# Mirror_ctrl_v1.net
KiCad netlist of a schematic drawn in EAGLE
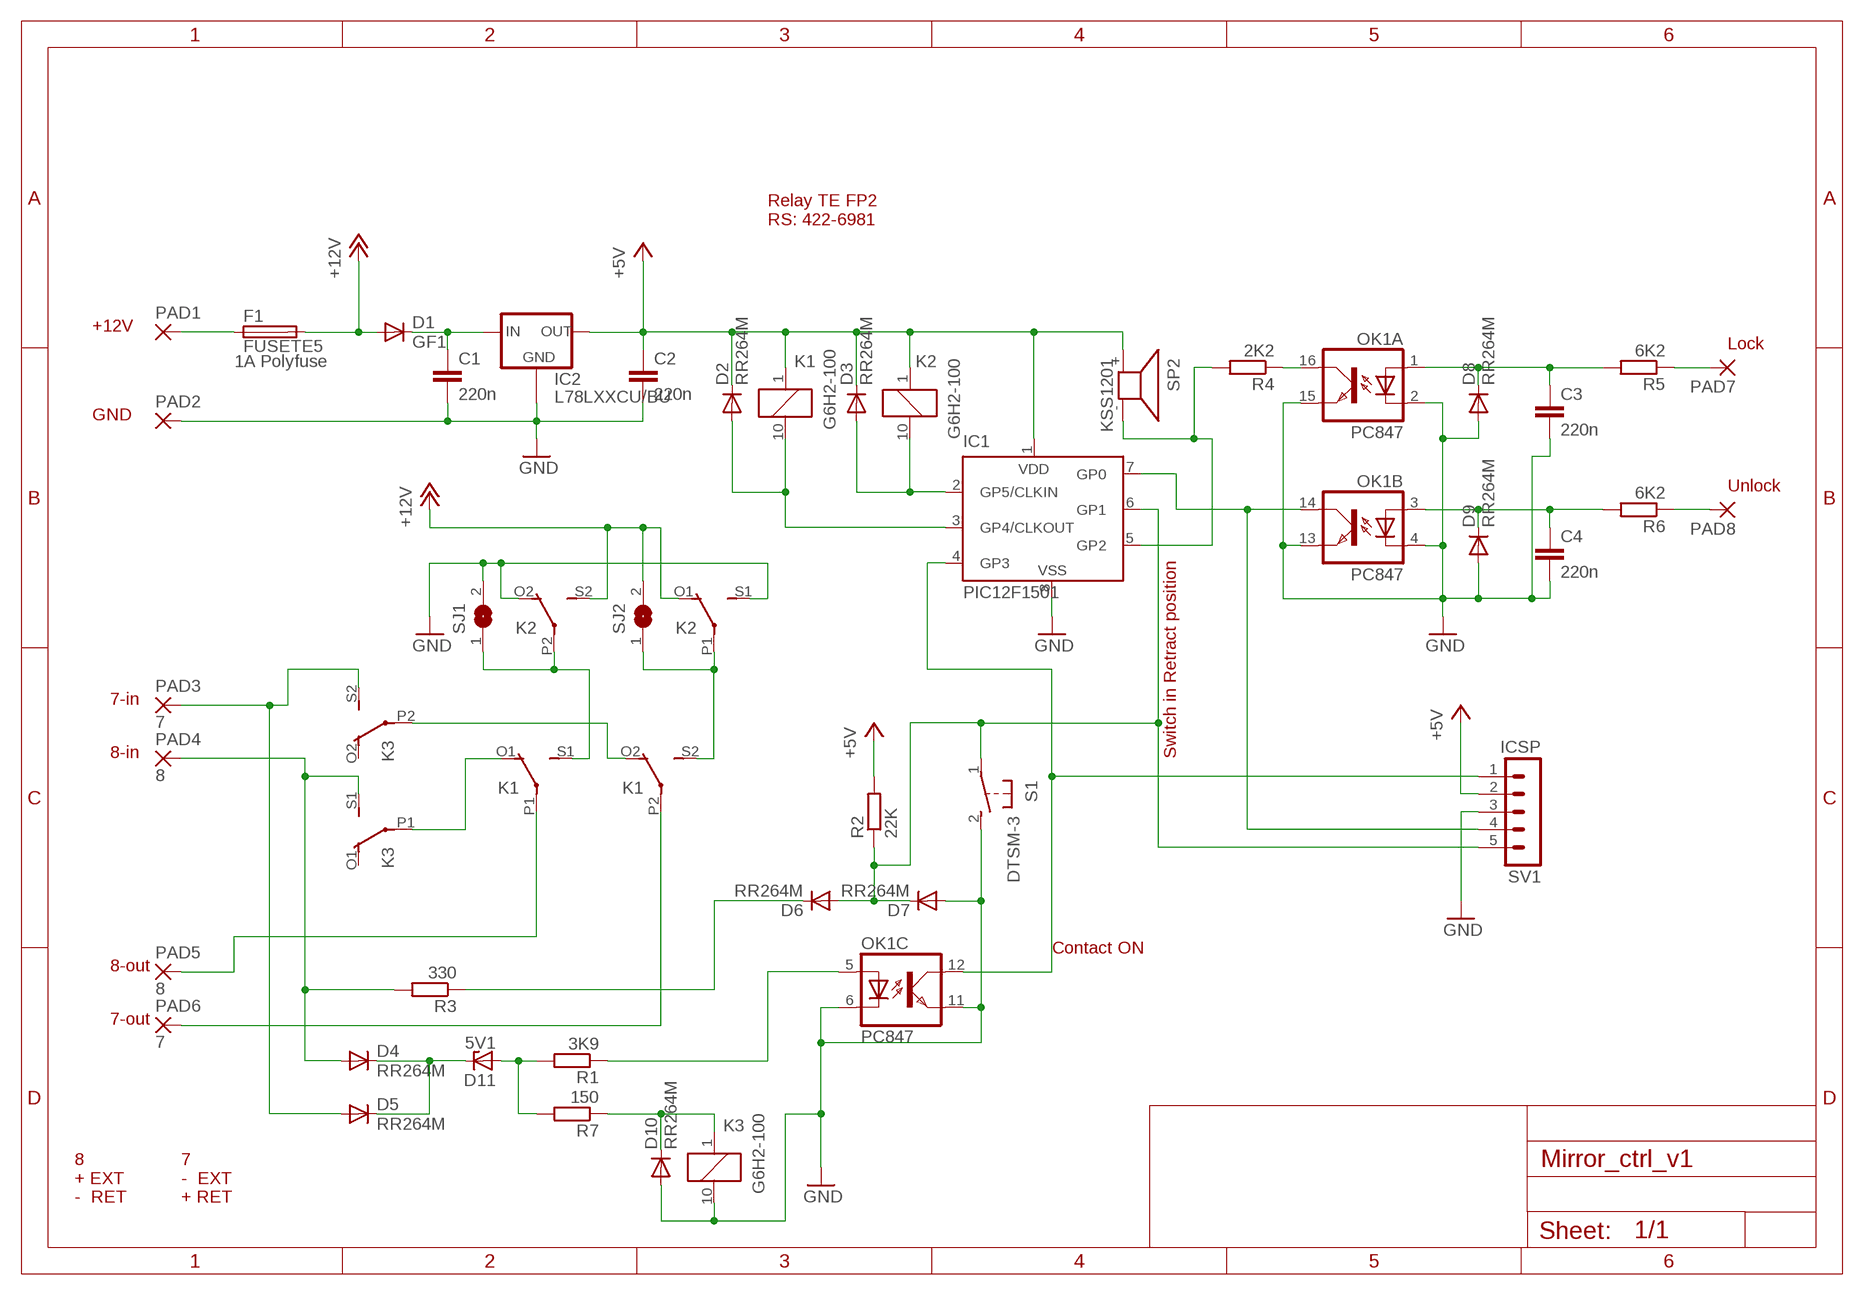
[diagram p0: schematic, sheet 1]

(export (version "E")
  (design (tool "Eeschema 10.0.6"))
  (components
    (comp (ref "C1")
      (value "220n")
      (footprint "eagle-import:C1206")
      (libsource (lib "eagle-import") (part "C-EUC1206"))
    )
    (comp (ref "C2")
      (value "220n")
      (footprint "eagle-import:C1206")
      (libsource (lib "eagle-import") (part "C-EUC1206"))
    )
    (comp (ref "C3")
      (value "220n")
      (footprint "eagle-import:C1206")
      (libsource (lib "eagle-import") (part "C-EUC1206"))
    )
    (comp (ref "C4")
      (value "220n")
      (footprint "eagle-import:C1206")
      (libsource (lib "eagle-import") (part "C-EUC1206"))
    )
    (comp (ref "D1")
      (value "GF1")
      (footprint "eagle-import:DO214BA")
      (libsource (lib "eagle-import") (part "DIODE-DO214BA"))
    )
    (comp (ref "D2")
      (value "RR264M")
      (footprint "eagle-import:SOD-123_MINI-SMA")
      (libsource (lib "eagle-import") (part "CGRM400-G1"))
    )
    (comp (ref "D3")
      (value "RR264M")
      (footprint "eagle-import:SOD-123_MINI-SMA")
      (libsource (lib "eagle-import") (part "CGRM400-G1"))
    )
    (comp (ref "D4")
      (value "RR264M")
      (footprint "eagle-import:SOD-123_MINI-SMA")
      (libsource (lib "eagle-import") (part "CGRM400-G1"))
    )
    (comp (ref "D5")
      (value "RR264M")
      (footprint "eagle-import:SOD-123_MINI-SMA")
      (libsource (lib "eagle-import") (part "CGRM400-G1"))
    )
    (comp (ref "D6")
      (value "RR264M")
      (footprint "eagle-import:SOD-123_MINI-SMA")
      (libsource (lib "eagle-import") (part "CGRM400-G1"))
    )
    (comp (ref "D7")
      (value "RR264M")
      (footprint "eagle-import:SOD-123_MINI-SMA")
      (libsource (lib "eagle-import") (part "CGRM400-G1"))
    )
    (comp (ref "D8")
      (value "RR264M")
      (footprint "eagle-import:SOD-123_MINI-SMA")
      (libsource (lib "eagle-import") (part "CGRM400-G1"))
    )
    (comp (ref "D9")
      (value "RR264M")
      (footprint "eagle-import:SOD-123_MINI-SMA")
      (libsource (lib "eagle-import") (part "CGRM400-G1"))
    )
    (comp (ref "D10")
      (value "RR264M")
      (footprint "eagle-import:SOD-123_MINI-SMA")
      (libsource (lib "eagle-import") (part "CGRM400-G1"))
    )
    (comp (ref "D11")
      (value "5V1")
      (footprint "eagle-import:SOD80C")
      (libsource (lib "eagle-import") (part "ZENER-DIODESOD80C"))
    )
    (comp (ref "F1")
      (value "FUSETE5")
      (footprint "eagle-import:TE5")
      (libsource (lib "eagle-import") (part "FUSETE5"))
    )
    (comp (ref "IC1")
      (value "PIC12F1501")
      (footprint "eagle-import:DIL8")
      (fields (field (name "MF") "MICROCHIP") (field (name "MPN") "PIC12F675-E/P"))
      (libsource (lib "eagle-import") (part "PIC12F6P75"))
    )
    (comp (ref "IC2")
      (value "L78LXXCU/BU")
      (footprint "eagle-import:SOT89")
      (libsource (lib "eagle-import") (part "L78LXXCU/BU"))
    )
    (comp (ref "K1")
      (value "G6H2-100")
      (footprint "eagle-import:G6H2-100")
      (libsource (lib "eagle-import") (part "G6H2-100"))
    )
    (comp (ref "K2")
      (value "G6H2-100")
      (footprint "eagle-import:G6H2-100")
      (libsource (lib "eagle-import") (part "G6H2-100"))
    )
    (comp (ref "K3")
      (value "G6H2-100")
      (footprint "eagle-import:G6H2-100")
      (libsource (lib "eagle-import") (part "G6H2-100"))
    )
    (comp (ref "OK1")
      (value "PC847")
      (footprint "eagle-import:DIL16")
      (libsource (lib "eagle-import") (part "PC847"))
    )
    (comp (ref "PAD1")
      (value "3,81/1,4")
      (footprint "eagle-import:3,81_1,4")
      (libsource (lib "eagle-import") (part "3,81/1,4"))
    )
    (comp (ref "PAD2")
      (value "3,81/1,4")
      (footprint "eagle-import:3,81_1,4")
      (libsource (lib "eagle-import") (part "3,81/1,4"))
    )
    (comp (ref "PAD3")
      (value "7")
      (footprint "eagle-import:3,81_1,4")
      (libsource (lib "eagle-import") (part "3,81/1,4"))
    )
    (comp (ref "PAD4")
      (value "8")
      (footprint "eagle-import:3,81_1,4")
      (libsource (lib "eagle-import") (part "3,81/1,4"))
    )
    (comp (ref "PAD5")
      (value "8")
      (footprint "eagle-import:3,81_1,4")
      (libsource (lib "eagle-import") (part "3,81/1,4"))
    )
    (comp (ref "PAD6")
      (value "7")
      (footprint "eagle-import:3,81_1,4")
      (libsource (lib "eagle-import") (part "3,81/1,4"))
    )
    (comp (ref "PAD7")
      (value "3,81/1,4")
      (footprint "eagle-import:3,81_1,4")
      (libsource (lib "eagle-import") (part "3,81/1,4"))
    )
    (comp (ref "PAD8")
      (value "3,81/1,4")
      (footprint "eagle-import:3,81_1,4")
      (libsource (lib "eagle-import") (part "3,81/1,4"))
    )
    (comp (ref "R1")
      (value "3K9")
      (footprint "eagle-import:R1206")
      (libsource (lib "eagle-import") (part "R-EU_R1206"))
    )
    (comp (ref "R2")
      (value "22K")
      (footprint "eagle-import:R1206")
      (libsource (lib "eagle-import") (part "R-EU_R1206"))
    )
    (comp (ref "R3")
      (value "330")
      (footprint "eagle-import:R1206")
      (libsource (lib "eagle-import") (part "R-EU_R1206"))
    )
    (comp (ref "R4")
      (value "2K2")
      (footprint "eagle-import:R1206")
      (libsource (lib "eagle-import") (part "R-EU_R1206"))
    )
    (comp (ref "R5")
      (value "6K2")
      (footprint "eagle-import:R1206")
      (libsource (lib "eagle-import") (part "R-EU_R1206"))
    )
    (comp (ref "R6")
      (value "6K2")
      (footprint "eagle-import:R1206")
      (libsource (lib "eagle-import") (part "R-EU_R1206"))
    )
    (comp (ref "R7")
      (value "150")
      (footprint "eagle-import:R1206")
      (libsource (lib "eagle-import") (part "R-EU_R1206"))
    )
    (comp (ref "S1")
      (value "DTSM-3")
      (footprint "eagle-import:DTSM-3")
      (libsource (lib "eagle-import") (part "DTSM-3"))
    )
    (comp (ref "SJ1") (value "SJ") (footprint "eagle-import:SJ") (libsource (lib "eagle-import") (part "SJ")))
    (comp (ref "SJ2") (value "SJ") (footprint "eagle-import:SJ") (libsource (lib "eagle-import") (part "SJ")))
    (comp (ref "SP2")
      (value "KSS1201")
      (footprint "eagle-import:KSS1201")
      (libsource (lib "eagle-import") (part "KSS1201"))
    )
    (comp (ref "SV1")
      (value "ICSP")
      (footprint "eagle-import:MA05-1")
      (libsource (lib "eagle-import") (part "MA05-1"))
    )
  )
  (nets
    (net (code "1") (name "+5V") (class "Default")
      (node (ref "C2") (pin "1") (pinfunction "1_1") (pintype "passive"))
      (node (ref "D2") (pin "C") (pinfunction "C_C") (pintype "passive"))
      (node (ref "D3") (pin "C") (pinfunction "C_C") (pintype "passive"))
      (node (ref "IC1") (pin "1") (pinfunction "VDD_1") (pintype "power_in"))
      (node (ref "IC2") (pin "1") (pinfunction "OUT_1") (pintype "passive"))
      (node (ref "K1") (pin "1") (pinfunction "1_1") (pintype "passive"))
      (node (ref "K2") (pin "1") (pinfunction "1_1") (pintype "passive"))
      (node (ref "R2") (pin "2") (pinfunction "2_2") (pintype "passive"))
      (node (ref "SP2") (pin "+") (pinfunction "1_+") (pintype "passive"))
      (node (ref "SV1") (pin "2") (pinfunction "2_2") (pintype "passive"))
    )
    (net (code "2") (name "+12V") (class "Default")
      (node (ref "D1") (pin "A") (pinfunction "A_A") (pintype "passive"))
      (node (ref "F1") (pin "2") (pinfunction "2_2") (pintype "passive"))
      (node (ref "K2") (pin "O1") (pinfunction "O_O1") (pintype "passive"))
      (node (ref "K2") (pin "S2") (pinfunction "S_S2") (pintype "passive"))
      (node (ref "SJ2") (pin "2") (pinfunction "2_2") (pintype "passive"))
    )
    (net (code "3") (name "GND") (class "Default")
      (node (ref "C1") (pin "2") (pinfunction "2_2") (pintype "passive"))
      (node (ref "C2") (pin "2") (pinfunction "2_2") (pintype "passive"))
      (node (ref "C3") (pin "2") (pinfunction "2_2") (pintype "passive"))
      (node (ref "C4") (pin "2") (pinfunction "2_2") (pintype "passive"))
      (node (ref "D10") (pin "A") (pinfunction "A_A") (pintype "passive"))
      (node (ref "D7") (pin "A") (pinfunction "A_A") (pintype "passive"))
      (node (ref "D8") (pin "A") (pinfunction "A_A") (pintype "passive"))
      (node (ref "D9") (pin "A") (pinfunction "A_A") (pintype "passive"))
      (node (ref "IC1") (pin "8") (pinfunction "VSS_8") (pintype "power_in"))
      (node (ref "IC2") (pin "4") (pinfunction "GND1_4") (pintype "input"))
      (node (ref "K2") (pin "O2") (pinfunction "O_O2") (pintype "passive"))
      (node (ref "K2") (pin "S1") (pinfunction "S_S1") (pintype "passive"))
      (node (ref "K3") (pin "10") (pinfunction "2_10") (pintype "passive"))
      (node (ref "OK1") (pin "11") (pinfunction "EMIT_11") (pintype "passive"))
      (node (ref "OK1") (pin "13") (pinfunction "EMIT_13") (pintype "passive"))
      (node (ref "OK1") (pin "15") (pinfunction "EMIT_15") (pintype "passive"))
      (node (ref "OK1") (pin "2") (pinfunction "C_2") (pintype "passive"))
      (node (ref "OK1") (pin "4") (pinfunction "C_4") (pintype "passive"))
      (node (ref "OK1") (pin "6") (pinfunction "C_6") (pintype "passive"))
      (node (ref "PAD2") (pin "1") (pinfunction "P_1") (pintype "passive"))
      (node (ref "S1") (pin "2") (pinfunction "2_2") (pintype "passive"))
      (node (ref "SJ1") (pin "2") (pinfunction "2_2") (pintype "passive"))
      (node (ref "SV1") (pin "3") (pinfunction "3_3") (pintype "passive"))
    )
    (net (code "4") (name "Net-(D6-PadC)") (class "Default")
      (node (ref "D6") (pin "C") (pinfunction "C_C") (pintype "passive"))
      (node (ref "R3") (pin "1") (pinfunction "1_1") (pintype "passive"))
    )
    (net (code "5") (name "Net-(D10-PadC)") (class "Default")
      (node (ref "D10") (pin "C") (pinfunction "C_C") (pintype "passive"))
      (node (ref "K3") (pin "1") (pinfunction "1_1") (pintype "passive"))
      (node (ref "R7") (pin "1") (pinfunction "1_1") (pintype "passive"))
    )
    (net (code "6") (name "Net-(D11-PadA)") (class "Default")
      (node (ref "D11") (pin "A") (pinfunction "A_A") (pintype "passive"))
      (node (ref "R1") (pin "2") (pinfunction "2_2") (pintype "passive"))
      (node (ref "R7") (pin "2") (pinfunction "2_2") (pintype "passive"))
    )
    (net (code "7") (name "Net-(D11-PadC)") (class "Default")
      (node (ref "D11") (pin "C") (pinfunction "C_C") (pintype "passive"))
      (node (ref "D4") (pin "C") (pinfunction "C_C") (pintype "passive"))
      (node (ref "D5") (pin "C") (pinfunction "C_C") (pintype "passive"))
    )
    (net (code "8") (name "Net-(IC1-GP0)") (class "Default")
      (node (ref "IC1") (pin "7") (pinfunction "GP0_7") (pintype "bidirectional"))
      (node (ref "OK1") (pin "14") (pinfunction "COL_14") (pintype "passive"))
      (node (ref "SV1") (pin "4") (pinfunction "4_4") (pintype "passive"))
    )
    (net (code "9") (name "Net-(IC1-GP1)") (class "Default")
      (node (ref "D6") (pin "A") (pinfunction "A_A") (pintype "passive"))
      (node (ref "D7") (pin "C") (pinfunction "C_C") (pintype "passive"))
      (node (ref "IC1") (pin "6") (pinfunction "GP1_6") (pintype "bidirectional"))
      (node (ref "R2") (pin "1") (pinfunction "1_1") (pintype "passive"))
      (node (ref "S1") (pin "1") (pinfunction "1_1") (pintype "passive"))
      (node (ref "SV1") (pin "5") (pinfunction "5_5") (pintype "passive"))
    )
    (net (code "10") (name "Net-(IC1-GP2)") (class "Default")
      (node (ref "IC1") (pin "5") (pinfunction "GP2_5") (pintype "bidirectional"))
      (node (ref "R4") (pin "2") (pinfunction "2_2") (pintype "passive"))
      (node (ref "SP2") (pin "-") (pinfunction "2_-") (pintype "passive"))
    )
    (net (code "11") (name "Net-(IC1-GP3)") (class "Default")
      (node (ref "IC1") (pin "4") (pinfunction "GP3_4") (pintype "input"))
      (node (ref "OK1") (pin "12") (pinfunction "COL_12") (pintype "passive"))
      (node (ref "SV1") (pin "1") (pinfunction "1_1") (pintype "passive"))
    )
    (net (code "12") (name "Net-(IC1-GP4{slash}CLKOUT)") (class "Default")
      (node (ref "D2") (pin "A") (pinfunction "A_A") (pintype "passive"))
      (node (ref "IC1") (pin "3") (pinfunction "GP4/CLKOUT_3") (pintype "bidirectional"))
      (node (ref "K1") (pin "10") (pinfunction "2_10") (pintype "passive"))
    )
    (net (code "13") (name "Net-(IC1-GP5{slash}CLKIN)") (class "Default")
      (node (ref "D3") (pin "A") (pinfunction "A_A") (pintype "passive"))
      (node (ref "IC1") (pin "2") (pinfunction "GP5/CLKIN_2") (pintype "bidirectional"))
      (node (ref "K2") (pin "10") (pinfunction "2_10") (pintype "passive"))
    )
    (net (code "14") (name "Net-(IC2-IN)") (class "Default")
      (node (ref "C1") (pin "1") (pinfunction "1_1") (pintype "passive"))
      (node (ref "D1") (pin "C") (pinfunction "C_C") (pintype "passive"))
      (node (ref "IC2") (pin "3") (pinfunction "IN_3") (pintype "input"))
    )
    (net (code "15") (name "Net-(K1B-O)") (class "Default")
      (node (ref "K1") (pin "O1") (pinfunction "O_O1") (pintype "passive"))
      (node (ref "K3") (pin "P1") (pinfunction "P_P1") (pintype "passive"))
    )
    (net (code "16") (name "Net-(K1B-P)") (class "Default")
      (node (ref "K1") (pin "P1") (pinfunction "P_P1") (pintype "passive"))
      (node (ref "PAD5") (pin "1") (pinfunction "P_1") (pintype "passive"))
    )
    (net (code "17") (name "Net-(K1B-S)") (class "Default")
      (node (ref "K1") (pin "S1") (pinfunction "S_S1") (pintype "passive"))
      (node (ref "K2") (pin "P2") (pinfunction "P_P2") (pintype "passive"))
      (node (ref "SJ1") (pin "1") (pinfunction "1_1") (pintype "passive"))
    )
    (net (code "18") (name "Net-(K1C-O)") (class "Default")
      (node (ref "K1") (pin "O2") (pinfunction "O_O2") (pintype "passive"))
      (node (ref "K3") (pin "P2") (pinfunction "P_P2") (pintype "passive"))
    )
    (net (code "19") (name "Net-(K1C-P)") (class "Default")
      (node (ref "K1") (pin "P2") (pinfunction "P_P2") (pintype "passive"))
      (node (ref "PAD6") (pin "1") (pinfunction "P_1") (pintype "passive"))
    )
    (net (code "20") (name "Net-(K1C-S)") (class "Default")
      (node (ref "K1") (pin "S2") (pinfunction "S_S2") (pintype "passive"))
      (node (ref "K2") (pin "P1") (pinfunction "P_P1") (pintype "passive"))
      (node (ref "SJ2") (pin "1") (pinfunction "1_1") (pintype "passive"))
    )
    (net (code "21") (name "Net-(K3B-S)") (class "Default")
      (node (ref "D4") (pin "A") (pinfunction "A_A") (pintype "passive"))
      (node (ref "K3") (pin "S1") (pinfunction "S_S1") (pintype "passive"))
      (node (ref "PAD4") (pin "1") (pinfunction "P_1") (pintype "passive"))
      (node (ref "R3") (pin "2") (pinfunction "2_2") (pintype "passive"))
    )
    (net (code "22") (name "Net-(K3C-S)") (class "Default")
      (node (ref "D5") (pin "A") (pinfunction "A_A") (pintype "passive"))
      (node (ref "K3") (pin "S2") (pinfunction "S_S2") (pintype "passive"))
      (node (ref "PAD3") (pin "1") (pinfunction "P_1") (pintype "passive"))
    )
    (net (code "23") (name "Net-(OK1A-A)") (class "Default")
      (node (ref "C3") (pin "1") (pinfunction "1_1") (pintype "passive"))
      (node (ref "D8") (pin "C") (pinfunction "C_C") (pintype "passive"))
      (node (ref "OK1") (pin "1") (pinfunction "A_1") (pintype "passive"))
      (node (ref "R5") (pin "2") (pinfunction "2_2") (pintype "passive"))
    )
    (net (code "24") (name "Net-(OK1A-COL)") (class "Default")
      (node (ref "OK1") (pin "16") (pinfunction "COL_16") (pintype "passive"))
      (node (ref "R4") (pin "1") (pinfunction "1_1") (pintype "passive"))
    )
    (net (code "25") (name "Net-(OK1B-A)") (class "Default")
      (node (ref "C4") (pin "1") (pinfunction "1_1") (pintype "passive"))
      (node (ref "D9") (pin "C") (pinfunction "C_C") (pintype "passive"))
      (node (ref "OK1") (pin "3") (pinfunction "A_3") (pintype "passive"))
      (node (ref "R6") (pin "2") (pinfunction "2_2") (pintype "passive"))
    )
    (net (code "26") (name "Net-(OK1C-A)") (class "Default")
      (node (ref "OK1") (pin "5") (pinfunction "A_5") (pintype "passive"))
      (node (ref "R1") (pin "1") (pinfunction "1_1") (pintype "passive"))
    )
    (net (code "27") (name "Net-(PAD1-P)") (class "Default")
      (node (ref "F1") (pin "1") (pinfunction "1_1") (pintype "passive"))
      (node (ref "PAD1") (pin "1") (pinfunction "P_1") (pintype "passive"))
    )
    (net (code "28") (name "Net-(PAD7-P)") (class "Default")
      (node (ref "PAD7") (pin "1") (pinfunction "P_1") (pintype "passive"))
      (node (ref "R5") (pin "1") (pinfunction "1_1") (pintype "passive"))
    )
    (net (code "29") (name "Net-(PAD8-P)") (class "Default")
      (node (ref "PAD8") (pin "1") (pinfunction "P_1") (pintype "passive"))
      (node (ref "R6") (pin "1") (pinfunction "1_1") (pintype "passive"))
    )
    (net (code "30") (name "unconnected-(IC2-GND-Pad2)") (class "Default")
      (node (ref "IC2") (pin "2") (pinfunction "GND_2") (pintype "input"))
    )
    (net (code "31") (name "unconnected-(K3B-O-PadO1)") (class "Default")
      (node (ref "K3") (pin "O1") (pinfunction "O_O1") (pintype "passive"))
    )
    (net (code "32") (name "unconnected-(K3C-O-PadO2)") (class "Default")
      (node (ref "K3") (pin "O2") (pinfunction "O_O2") (pintype "passive"))
    )
  )
)
